# esquema.net
KiCad netlist of a schematic drawn in EAGLE
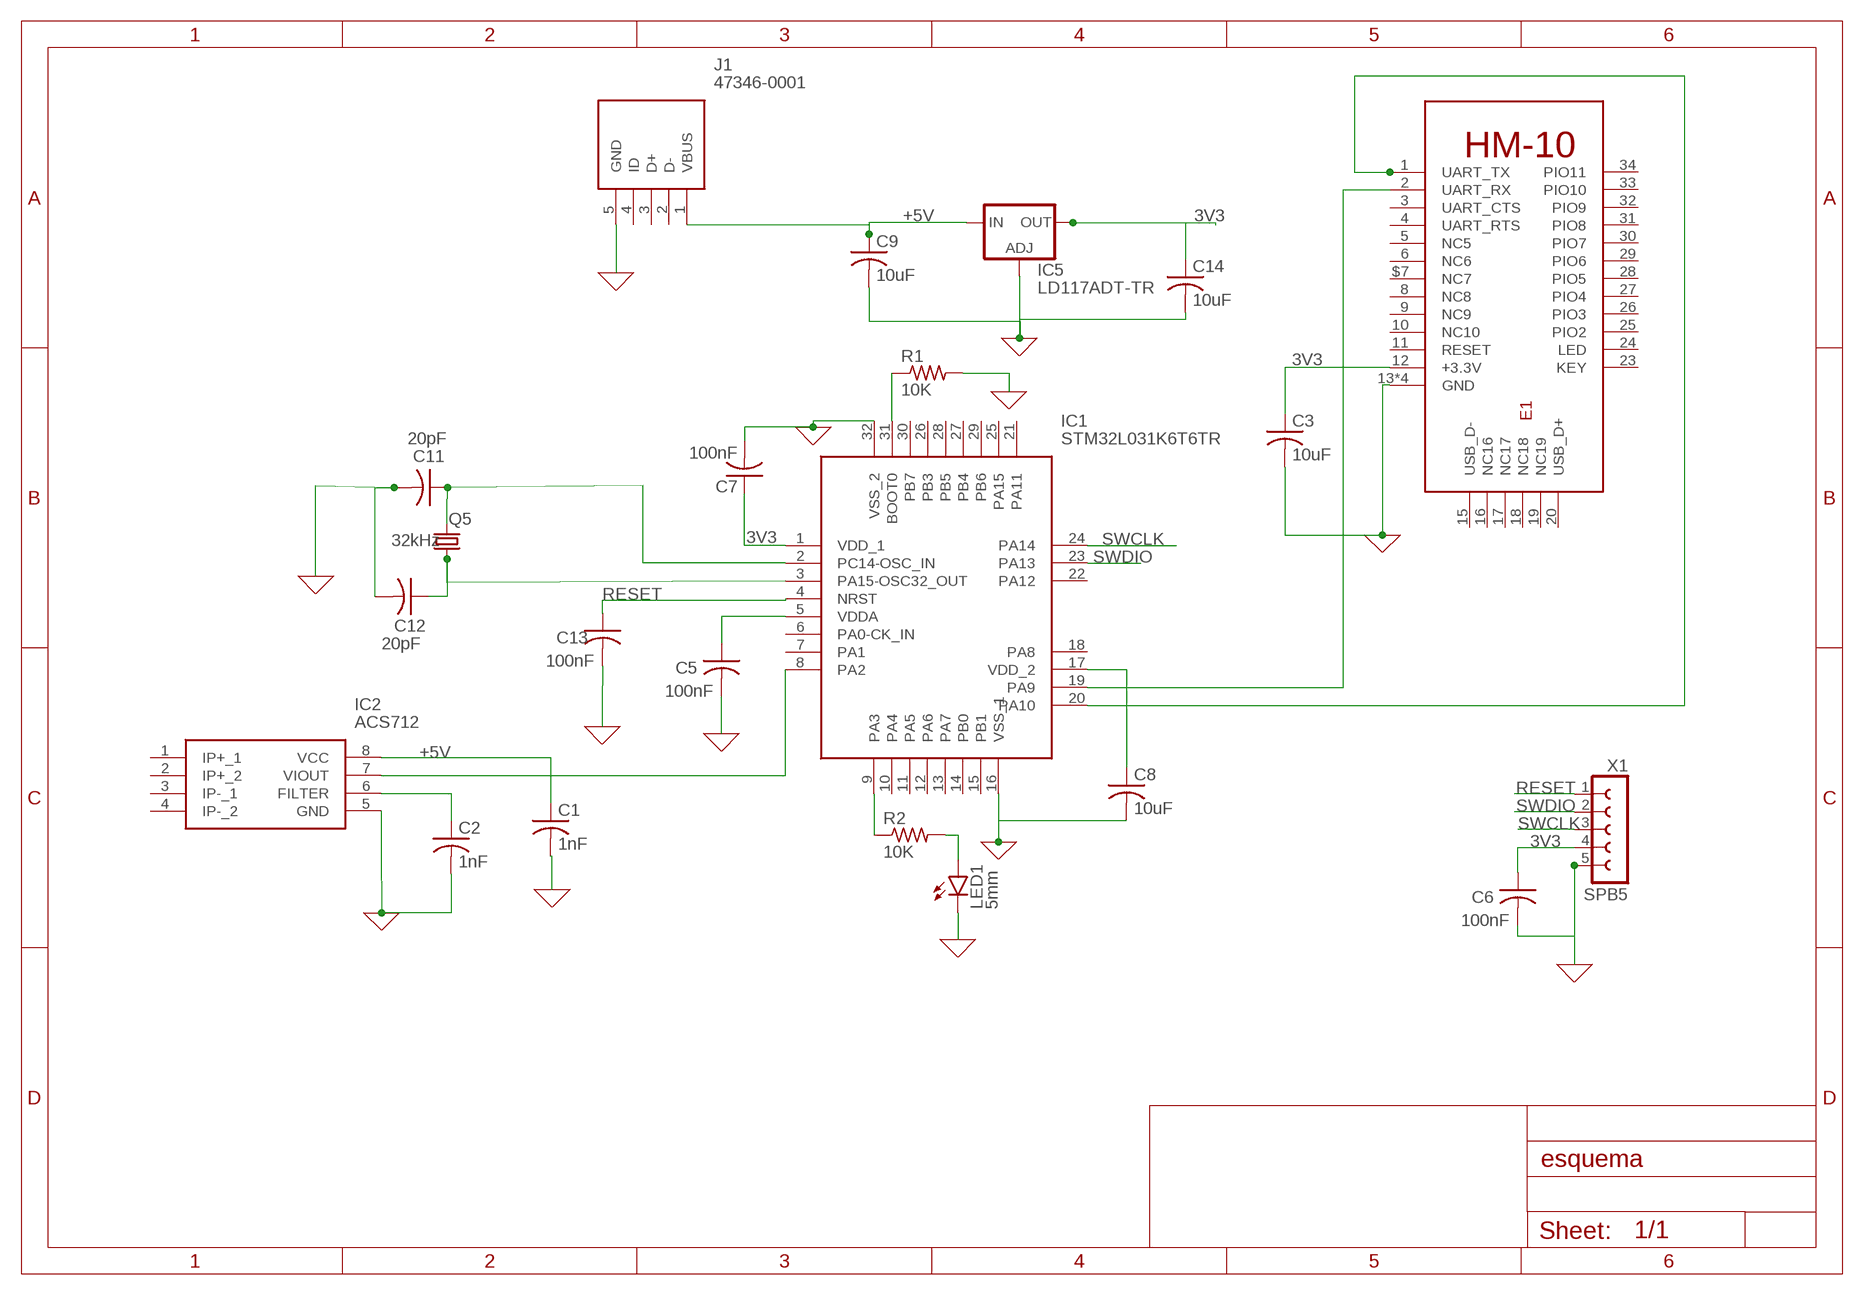
[diagram p0: schematic, sheet 1]

(export (version "E")
  (design (tool "Eeschema 10.0.6"))
  (components
    (comp (ref "C1")
      (value "1nF")
      (footprint "eagle-import:C0805")
      (libsource (lib "eagle-import") (part "C-USC0805"))
    )
    (comp (ref "C2")
      (value "1nF")
      (footprint "eagle-import:C0805")
      (libsource (lib "eagle-import") (part "C-USC0805"))
    )
    (comp (ref "C3")
      (value "10uF")
      (footprint "eagle-import:C0805")
      (libsource (lib "eagle-import") (part "C-USC0805"))
    )
    (comp (ref "C5")
      (value "100nF")
      (footprint "eagle-import:C0805")
      (libsource (lib "eagle-import") (part "C-USC0805"))
    )
    (comp (ref "C6")
      (value "100nF")
      (footprint "eagle-import:C0805")
      (libsource (lib "eagle-import") (part "C-USC0805"))
    )
    (comp (ref "C7")
      (value "100nF")
      (footprint "eagle-import:C0805")
      (libsource (lib "eagle-import") (part "C-USC0805"))
    )
    (comp (ref "C8")
      (value "10uF")
      (footprint "eagle-import:C0805")
      (libsource (lib "eagle-import") (part "C-USC0805"))
    )
    (comp (ref "C9")
      (value "10uF")
      (footprint "eagle-import:C0805")
      (libsource (lib "eagle-import") (part "C-USC0805"))
    )
    (comp (ref "C11")
      (value "20pF")
      (footprint "eagle-import:C0805")
      (libsource (lib "eagle-import") (part "C-USC0805"))
    )
    (comp (ref "C12")
      (value "20pF")
      (footprint "eagle-import:C0805")
      (libsource (lib "eagle-import") (part "C-USC0805"))
    )
    (comp (ref "C13")
      (value "100nF")
      (footprint "eagle-import:C0805")
      (libsource (lib "eagle-import") (part "C-USC0805"))
    )
    (comp (ref "C14")
      (value "10uF")
      (footprint "eagle-import:C0805")
      (libsource (lib "eagle-import") (part "C-USC0805"))
    )
    (comp (ref "E1")
      (value "HM-10-BOARD")
      (footprint "eagle-import:26.9X13X2.2_BOARD")
      (libsource (lib "eagle-import") (part "HM-10-BOARD"))
    )
    (comp (ref "IC1")
      (value "STM32L031K6T6TR")
      (footprint "eagle-import:QFP80P900X900X160-32N")
      (fields (field (name "MOUSER_PART_NUMBER") "511-STM32L031K6T6TR"))
      (libsource (lib "eagle-import") (part "STM32L031K6T6TR"))
    )
    (comp (ref "IC2")
      (value "ACS712")
      (footprint "eagle-import:SOIC127P600X175-8N")
      (libsource (lib "eagle-import") (part "ACS712"))
    )
    (comp (ref "IC5")
      (value "LD117ADT-TR")
      (footprint "eagle-import:DPACK")
      (libsource (lib "eagle-import") (part "LD117A?DT-TR"))
    )
    (comp (ref "J1")
      (value "47346-0001")
      (footprint "eagle-import:47346-0001")
      (fields (field (name "MOUSER_PART_NUMBER") "538-47346-0001"))
      (libsource (lib "eagle-import") (part "47346-0001"))
    )
    (comp (ref "LED1")
      (value "5mm")
      (footprint "eagle-import:LED5MM")
      (libsource (lib "eagle-import") (part "LED5MM"))
    )
    (comp (ref "Q5")
      (value "32kHz")
      (footprint "eagle-import:HC49_S")
      (libsource (lib "eagle-import") (part "CRYSTALHC49S"))
    )
    (comp (ref "R1")
      (value "10K")
      (footprint "eagle-import:1812X7R")
      (libsource (lib "eagle-import") (part "R-US_1812X7R"))
    )
    (comp (ref "R2")
      (value "10K")
      (footprint "eagle-import:1812X7R")
      (libsource (lib "eagle-import") (part "R-US_1812X7R"))
    )
    (comp (ref "X1")
      (value "SPB5")
      (footprint "eagle-import:SPB5")
      (libsource (lib "eagle-import") (part "SPB5"))
    )
  )
  (nets
    (net (code "1") (name "/+5V") (class "Default")
      (node (ref "C9") (pin "1") (pinfunction "1_1") (pintype "passive"))
      (node (ref "IC5") (pin "3") (pinfunction "IN_3") (pintype "input"))
      (node (ref "J1") (pin "1") (pinfunction "VBUS_1") (pintype "bidirectional"))
    )
    (net (code "2") (name "/3V3") (class "Default")
      (node (ref "C14") (pin "1") (pinfunction "1_1") (pintype "passive"))
      (node (ref "IC5") (pin "4") (pinfunction "OUT_4") (pintype "passive"))
    )
    (net (code "3") (name "/RESET") (class "Default")
      (node (ref "X1") (pin "1") (pinfunction "1_1") (pintype "passive"))
    )
    (net (code "4") (name "/SWCLK") (class "Default")
      (node (ref "X1") (pin "3") (pinfunction "3_3") (pintype "passive"))
    )
    (net (code "5") (name "/SWDIO") (class "Default")
      (node (ref "X1") (pin "2") (pinfunction "2_2") (pintype "passive"))
    )
    (net (code "6") (name "GND") (class "Default")
      (node (ref "C1") (pin "2") (pinfunction "2_2") (pintype "passive"))
      (node (ref "C11") (pin "2") (pinfunction "2_2") (pintype "passive"))
      (node (ref "C12") (pin "2") (pinfunction "2_2") (pintype "passive"))
      (node (ref "C13") (pin "2") (pinfunction "2_2") (pintype "passive"))
      (node (ref "C14") (pin "2") (pinfunction "2_2") (pintype "passive"))
      (node (ref "C2") (pin "2") (pinfunction "2_2") (pintype "passive"))
      (node (ref "C3") (pin "2") (pinfunction "2_2") (pintype "passive"))
      (node (ref "C5") (pin "2") (pinfunction "2_2") (pintype "passive"))
      (node (ref "C6") (pin "2") (pinfunction "2_2") (pintype "passive"))
      (node (ref "C7") (pin "2") (pinfunction "2_2") (pintype "passive"))
      (node (ref "C8") (pin "2") (pinfunction "2_2") (pintype "passive"))
      (node (ref "C9") (pin "2") (pinfunction "2_2") (pintype "passive"))
      (node (ref "E1") (pin "13") (pinfunction "GND_13") (pintype "bidirectional"))
      (node (ref "E1") (pin "14") (pinfunction "GND_14") (pintype "bidirectional"))
      (node (ref "E1") (pin "21") (pinfunction "GND_21") (pintype "bidirectional"))
      (node (ref "E1") (pin "22") (pinfunction "GND_22") (pintype "bidirectional"))
      (node (ref "IC1") (pin "16") (pinfunction "VSS_1_16") (pintype "bidirectional"))
      (node (ref "IC1") (pin "32") (pinfunction "VSS_2_32") (pintype "bidirectional"))
      (node (ref "IC2") (pin "5") (pinfunction "GND_5") (pintype "bidirectional"))
      (node (ref "IC5") (pin "1") (pinfunction "ADJ_1") (pintype "input"))
      (node (ref "J1") (pin "5") (pinfunction "GND_5") (pintype "bidirectional"))
      (node (ref "LED1") (pin "K") (pinfunction "C_K") (pintype "passive"))
      (node (ref "R1") (pin "2") (pinfunction "2_2") (pintype "passive"))
      (node (ref "X1") (pin "5") (pinfunction "5_5") (pintype "passive"))
    )
    (net (code "7") (name "Net-(C6-Pad1)") (class "Default")
      (node (ref "C6") (pin "1") (pinfunction "1_1") (pintype "passive"))
      (node (ref "X1") (pin "4") (pinfunction "4_4") (pintype "passive"))
    )
    (net (code "8") (name "Net-(E1-+3.3V)") (class "Default")
      (node (ref "C3") (pin "1") (pinfunction "1_1") (pintype "passive"))
      (node (ref "E1") (pin "12") (pinfunction "+3.3V_12") (pintype "bidirectional"))
    )
    (net (code "9") (name "Net-(E1-UART_RX)") (class "Default")
      (node (ref "E1") (pin "2") (pinfunction "UART_RX_2") (pintype "bidirectional"))
      (node (ref "IC1") (pin "19") (pinfunction "PA9_19") (pintype "bidirectional"))
    )
    (net (code "10") (name "Net-(E1-UART_TX)") (class "Default")
      (node (ref "E1") (pin "1") (pinfunction "UART_TX_1") (pintype "bidirectional"))
      (node (ref "IC1") (pin "20") (pinfunction "PA10_20") (pintype "bidirectional"))
    )
    (net (code "11") (name "Net-(IC1-BOOT0)") (class "Default")
      (node (ref "IC1") (pin "31") (pinfunction "BOOT0_31") (pintype "bidirectional"))
      (node (ref "R1") (pin "1") (pinfunction "1_1") (pintype "passive"))
    )
    (net (code "12") (name "Net-(IC1-NRST)") (class "Default")
      (node (ref "C13") (pin "1") (pinfunction "1_1") (pintype "passive"))
      (node (ref "IC1") (pin "4") (pinfunction "NRST_4") (pintype "bidirectional"))
    )
    (net (code "13") (name "Net-(IC1-PA2)") (class "Default")
      (node (ref "IC1") (pin "8") (pinfunction "PA2_8") (pintype "bidirectional"))
      (node (ref "IC2") (pin "7") (pinfunction "VIOUT_7") (pintype "bidirectional"))
    )
    (net (code "14") (name "Net-(IC1-PA3)") (class "Default")
      (node (ref "IC1") (pin "9") (pinfunction "PA3_9") (pintype "bidirectional"))
      (node (ref "R2") (pin "1") (pinfunction "1_1") (pintype "passive"))
    )
    (net (code "15") (name "Net-(IC1-PA15-OSC32_OUT)") (class "Default")
      (node (ref "C12") (pin "1") (pinfunction "1_1") (pintype "passive"))
      (node (ref "IC1") (pin "3") (pinfunction "PA15-OSC32_OUT_3") (pintype "bidirectional"))
      (node (ref "Q5") (pin "1") (pinfunction "1_1") (pintype "passive"))
    )
    (net (code "16") (name "Net-(IC1-PC14-OSC_IN)") (class "Default")
      (node (ref "C11") (pin "1") (pinfunction "1_1") (pintype "passive"))
      (node (ref "IC1") (pin "2") (pinfunction "PC14-OSC_IN_2") (pintype "bidirectional"))
      (node (ref "Q5") (pin "2") (pinfunction "2_2") (pintype "passive"))
    )
    (net (code "17") (name "Net-(IC1-VDDA)") (class "Default")
      (node (ref "C5") (pin "1") (pinfunction "1_1") (pintype "passive"))
      (node (ref "IC1") (pin "5") (pinfunction "VDDA_5") (pintype "bidirectional"))
    )
    (net (code "18") (name "Net-(IC1-VDD_1)") (class "Default")
      (node (ref "C7") (pin "1") (pinfunction "1_1") (pintype "passive"))
      (node (ref "IC1") (pin "1") (pinfunction "VDD_1_1") (pintype "bidirectional"))
    )
    (net (code "19") (name "Net-(IC1-VDD_2)") (class "Default")
      (node (ref "C8") (pin "1") (pinfunction "1_1") (pintype "passive"))
      (node (ref "IC1") (pin "17") (pinfunction "VDD_2_17") (pintype "bidirectional"))
    )
    (net (code "20") (name "Net-(IC2-FILTER)") (class "Default")
      (node (ref "C2") (pin "1") (pinfunction "1_1") (pintype "passive"))
      (node (ref "IC2") (pin "6") (pinfunction "FILTER_6") (pintype "bidirectional"))
    )
    (net (code "21") (name "Net-(IC2-VCC)") (class "Default")
      (node (ref "C1") (pin "1") (pinfunction "1_1") (pintype "passive"))
      (node (ref "IC2") (pin "8") (pinfunction "VCC_8") (pintype "bidirectional"))
    )
    (net (code "22") (name "Net-(LED1-PadA)") (class "Default")
      (node (ref "LED1") (pin "A") (pinfunction "A_A") (pintype "passive"))
      (node (ref "R2") (pin "2") (pinfunction "2_2") (pintype "passive"))
    )
    (net (code "23") (name "unconnected-(E1-KEY-Pad23)") (class "Default")
      (node (ref "E1") (pin "23") (pinfunction "KEY_23") (pintype "bidirectional"))
    )
    (net (code "24") (name "unconnected-(E1-LED-Pad24)") (class "Default")
      (node (ref "E1") (pin "24") (pinfunction "LED_24") (pintype "bidirectional"))
    )
    (net (code "25") (name "unconnected-(E1-NC5-Pad5)") (class "Default")
      (node (ref "E1") (pin "5") (pinfunction "NC5_5") (pintype "bidirectional"))
    )
    (net (code "26") (name "unconnected-(E1-NC6-Pad6)") (class "Default")
      (node (ref "E1") (pin "6") (pinfunction "NC6_6") (pintype "bidirectional"))
    )
    (net (code "27") (name "unconnected-(E1-NC7-Pad$7)") (class "Default")
      (node (ref "E1") (pin "$7") (pinfunction "NC7_$7") (pintype "bidirectional"))
    )
    (net (code "28") (name "unconnected-(E1-NC8-Pad8)") (class "Default")
      (node (ref "E1") (pin "8") (pinfunction "NC8_8") (pintype "bidirectional"))
    )
    (net (code "29") (name "unconnected-(E1-NC9-Pad9)") (class "Default")
      (node (ref "E1") (pin "9") (pinfunction "NC9_9") (pintype "bidirectional"))
    )
    (net (code "30") (name "unconnected-(E1-NC10-Pad10)") (class "Default")
      (node (ref "E1") (pin "10") (pinfunction "NC10_10") (pintype "bidirectional"))
    )
    (net (code "31") (name "unconnected-(E1-NC16-Pad16)") (class "Default")
      (node (ref "E1") (pin "16") (pinfunction "NC16_16") (pintype "bidirectional"))
    )
    (net (code "32") (name "unconnected-(E1-NC17-Pad17)") (class "Default")
      (node (ref "E1") (pin "17") (pinfunction "NC17_17") (pintype "bidirectional"))
    )
    (net (code "33") (name "unconnected-(E1-NC18-Pad18)") (class "Default")
      (node (ref "E1") (pin "18") (pinfunction "NC18_18") (pintype "bidirectional"))
    )
    (net (code "34") (name "unconnected-(E1-NC19-Pad19)") (class "Default")
      (node (ref "E1") (pin "19") (pinfunction "NC19_19") (pintype "bidirectional"))
    )
    (net (code "35") (name "unconnected-(E1-PIO2-Pad25)") (class "Default")
      (node (ref "E1") (pin "25") (pinfunction "PIO2_25") (pintype "bidirectional"))
    )
    (net (code "36") (name "unconnected-(E1-PIO3-Pad26)") (class "Default")
      (node (ref "E1") (pin "26") (pinfunction "PIO3_26") (pintype "bidirectional"))
    )
    (net (code "37") (name "unconnected-(E1-PIO4-Pad27)") (class "Default")
      (node (ref "E1") (pin "27") (pinfunction "PIO4_27") (pintype "bidirectional"))
    )
    (net (code "38") (name "unconnected-(E1-PIO5-Pad28)") (class "Default")
      (node (ref "E1") (pin "28") (pinfunction "PIO5_28") (pintype "bidirectional"))
    )
    (net (code "39") (name "unconnected-(E1-PIO6-Pad29)") (class "Default")
      (node (ref "E1") (pin "29") (pinfunction "PIO6_29") (pintype "bidirectional"))
    )
    (net (code "40") (name "unconnected-(E1-PIO7-Pad30)") (class "Default")
      (node (ref "E1") (pin "30") (pinfunction "PIO7_30") (pintype "bidirectional"))
    )
    (net (code "41") (name "unconnected-(E1-PIO8-Pad31)") (class "Default")
      (node (ref "E1") (pin "31") (pinfunction "PIO8_31") (pintype "bidirectional"))
    )
    (net (code "42") (name "unconnected-(E1-PIO9-Pad32)") (class "Default")
      (node (ref "E1") (pin "32") (pinfunction "PIO9_32") (pintype "bidirectional"))
    )
    (net (code "43") (name "unconnected-(E1-PIO10-Pad33)") (class "Default")
      (node (ref "E1") (pin "33") (pinfunction "PIO10_33") (pintype "bidirectional"))
    )
    (net (code "44") (name "unconnected-(E1-PIO11-Pad34)") (class "Default")
      (node (ref "E1") (pin "34") (pinfunction "PIO11_34") (pintype "bidirectional"))
    )
    (net (code "45") (name "unconnected-(E1-RESET-Pad11)") (class "Default")
      (node (ref "E1") (pin "11") (pinfunction "RESET_11") (pintype "bidirectional"))
    )
    (net (code "46") (name "unconnected-(E1-UART_CTS-Pad3)") (class "Default")
      (node (ref "E1") (pin "3") (pinfunction "UART_CTS_3") (pintype "bidirectional"))
    )
    (net (code "47") (name "unconnected-(E1-UART_RTS-Pad4)") (class "Default")
      (node (ref "E1") (pin "4") (pinfunction "UART_RTS_4") (pintype "bidirectional"))
    )
    (net (code "48") (name "unconnected-(E1-USB_D+-Pad20)") (class "Default")
      (node (ref "E1") (pin "20") (pinfunction "USB_D+_20") (pintype "bidirectional"))
    )
    (net (code "49") (name "unconnected-(E1-USB_D--Pad15)") (class "Default")
      (node (ref "E1") (pin "15") (pinfunction "USB_D-_15") (pintype "bidirectional"))
    )
    (net (code "50") (name "unconnected-(IC1-PA0-CK_IN-Pad6)") (class "Default")
      (node (ref "IC1") (pin "6") (pinfunction "PA0-CK_IN_6") (pintype "bidirectional"))
    )
    (net (code "51") (name "unconnected-(IC1-PA1-Pad7)") (class "Default")
      (node (ref "IC1") (pin "7") (pinfunction "PA1_7") (pintype "bidirectional"))
    )
    (net (code "52") (name "unconnected-(IC1-PA4-Pad10)") (class "Default")
      (node (ref "IC1") (pin "10") (pinfunction "PA4_10") (pintype "bidirectional"))
    )
    (net (code "53") (name "unconnected-(IC1-PA5-Pad11)") (class "Default")
      (node (ref "IC1") (pin "11") (pinfunction "PA5_11") (pintype "bidirectional"))
    )
    (net (code "54") (name "unconnected-(IC1-PA6-Pad12)") (class "Default")
      (node (ref "IC1") (pin "12") (pinfunction "PA6_12") (pintype "bidirectional"))
    )
    (net (code "55") (name "unconnected-(IC1-PA7-Pad13)") (class "Default")
      (node (ref "IC1") (pin "13") (pinfunction "PA7_13") (pintype "bidirectional"))
    )
    (net (code "56") (name "unconnected-(IC1-PA8-Pad18)") (class "Default")
      (node (ref "IC1") (pin "18") (pinfunction "PA8_18") (pintype "bidirectional"))
    )
    (net (code "57") (name "unconnected-(IC1-PA11-Pad21)") (class "Default")
      (node (ref "IC1") (pin "21") (pinfunction "PA11_21") (pintype "bidirectional"))
    )
    (net (code "58") (name "unconnected-(IC1-PA12-Pad22)") (class "Default")
      (node (ref "IC1") (pin "22") (pinfunction "PA12_22") (pintype "bidirectional"))
    )
    (net (code "59") (name "unconnected-(IC1-PA13-Pad23)") (class "Default")
      (node (ref "IC1") (pin "23") (pinfunction "PA13_23") (pintype "bidirectional"))
    )
    (net (code "60") (name "unconnected-(IC1-PA14-Pad24)") (class "Default")
      (node (ref "IC1") (pin "24") (pinfunction "PA14_24") (pintype "bidirectional"))
    )
    (net (code "61") (name "unconnected-(IC1-PA15-Pad25)") (class "Default")
      (node (ref "IC1") (pin "25") (pinfunction "PA15_25") (pintype "bidirectional"))
    )
    (net (code "62") (name "unconnected-(IC1-PB0-Pad14)") (class "Default")
      (node (ref "IC1") (pin "14") (pinfunction "PB0_14") (pintype "bidirectional"))
    )
    (net (code "63") (name "unconnected-(IC1-PB1-Pad15)") (class "Default")
      (node (ref "IC1") (pin "15") (pinfunction "PB1_15") (pintype "bidirectional"))
    )
    (net (code "64") (name "unconnected-(IC1-PB3-Pad26)") (class "Default")
      (node (ref "IC1") (pin "26") (pinfunction "PB3_26") (pintype "bidirectional"))
    )
    (net (code "65") (name "unconnected-(IC1-PB4-Pad27)") (class "Default")
      (node (ref "IC1") (pin "27") (pinfunction "PB4_27") (pintype "bidirectional"))
    )
    (net (code "66") (name "unconnected-(IC1-PB5-Pad28)") (class "Default")
      (node (ref "IC1") (pin "28") (pinfunction "PB5_28") (pintype "bidirectional"))
    )
    (net (code "67") (name "unconnected-(IC1-PB6-Pad29)") (class "Default")
      (node (ref "IC1") (pin "29") (pinfunction "PB6_29") (pintype "bidirectional"))
    )
    (net (code "68") (name "unconnected-(IC1-PB7-Pad30)") (class "Default")
      (node (ref "IC1") (pin "30") (pinfunction "PB7_30") (pintype "bidirectional"))
    )
    (net (code "69") (name "unconnected-(IC2-IP+_1-Pad1)") (class "Default")
      (node (ref "IC2") (pin "1") (pinfunction "IP+_1_1") (pintype "bidirectional"))
    )
    (net (code "70") (name "unconnected-(IC2-IP+_2-Pad2)") (class "Default")
      (node (ref "IC2") (pin "2") (pinfunction "IP+_2_2") (pintype "bidirectional"))
    )
    (net (code "71") (name "unconnected-(IC2-IP-_1-Pad3)") (class "Default")
      (node (ref "IC2") (pin "3") (pinfunction "IP-_1_3") (pintype "bidirectional"))
    )
    (net (code "72") (name "unconnected-(IC2-IP-_2-Pad4)") (class "Default")
      (node (ref "IC2") (pin "4") (pinfunction "IP-_2_4") (pintype "bidirectional"))
    )
    (net (code "73") (name "unconnected-(J1-D+-Pad3)") (class "Default")
      (node (ref "J1") (pin "3") (pinfunction "D+_3") (pintype "bidirectional"))
    )
    (net (code "74") (name "unconnected-(J1-D--Pad2)") (class "Default")
      (node (ref "J1") (pin "2") (pinfunction "D-_2") (pintype "bidirectional"))
    )
    (net (code "75") (name "unconnected-(J1-ID-Pad4)") (class "Default")
      (node (ref "J1") (pin "4") (pinfunction "ID_4") (pintype "bidirectional"))
    )
  )
)
